# Nu6509_v3.net
KiCad netlist of a schematic drawn in EAGLE
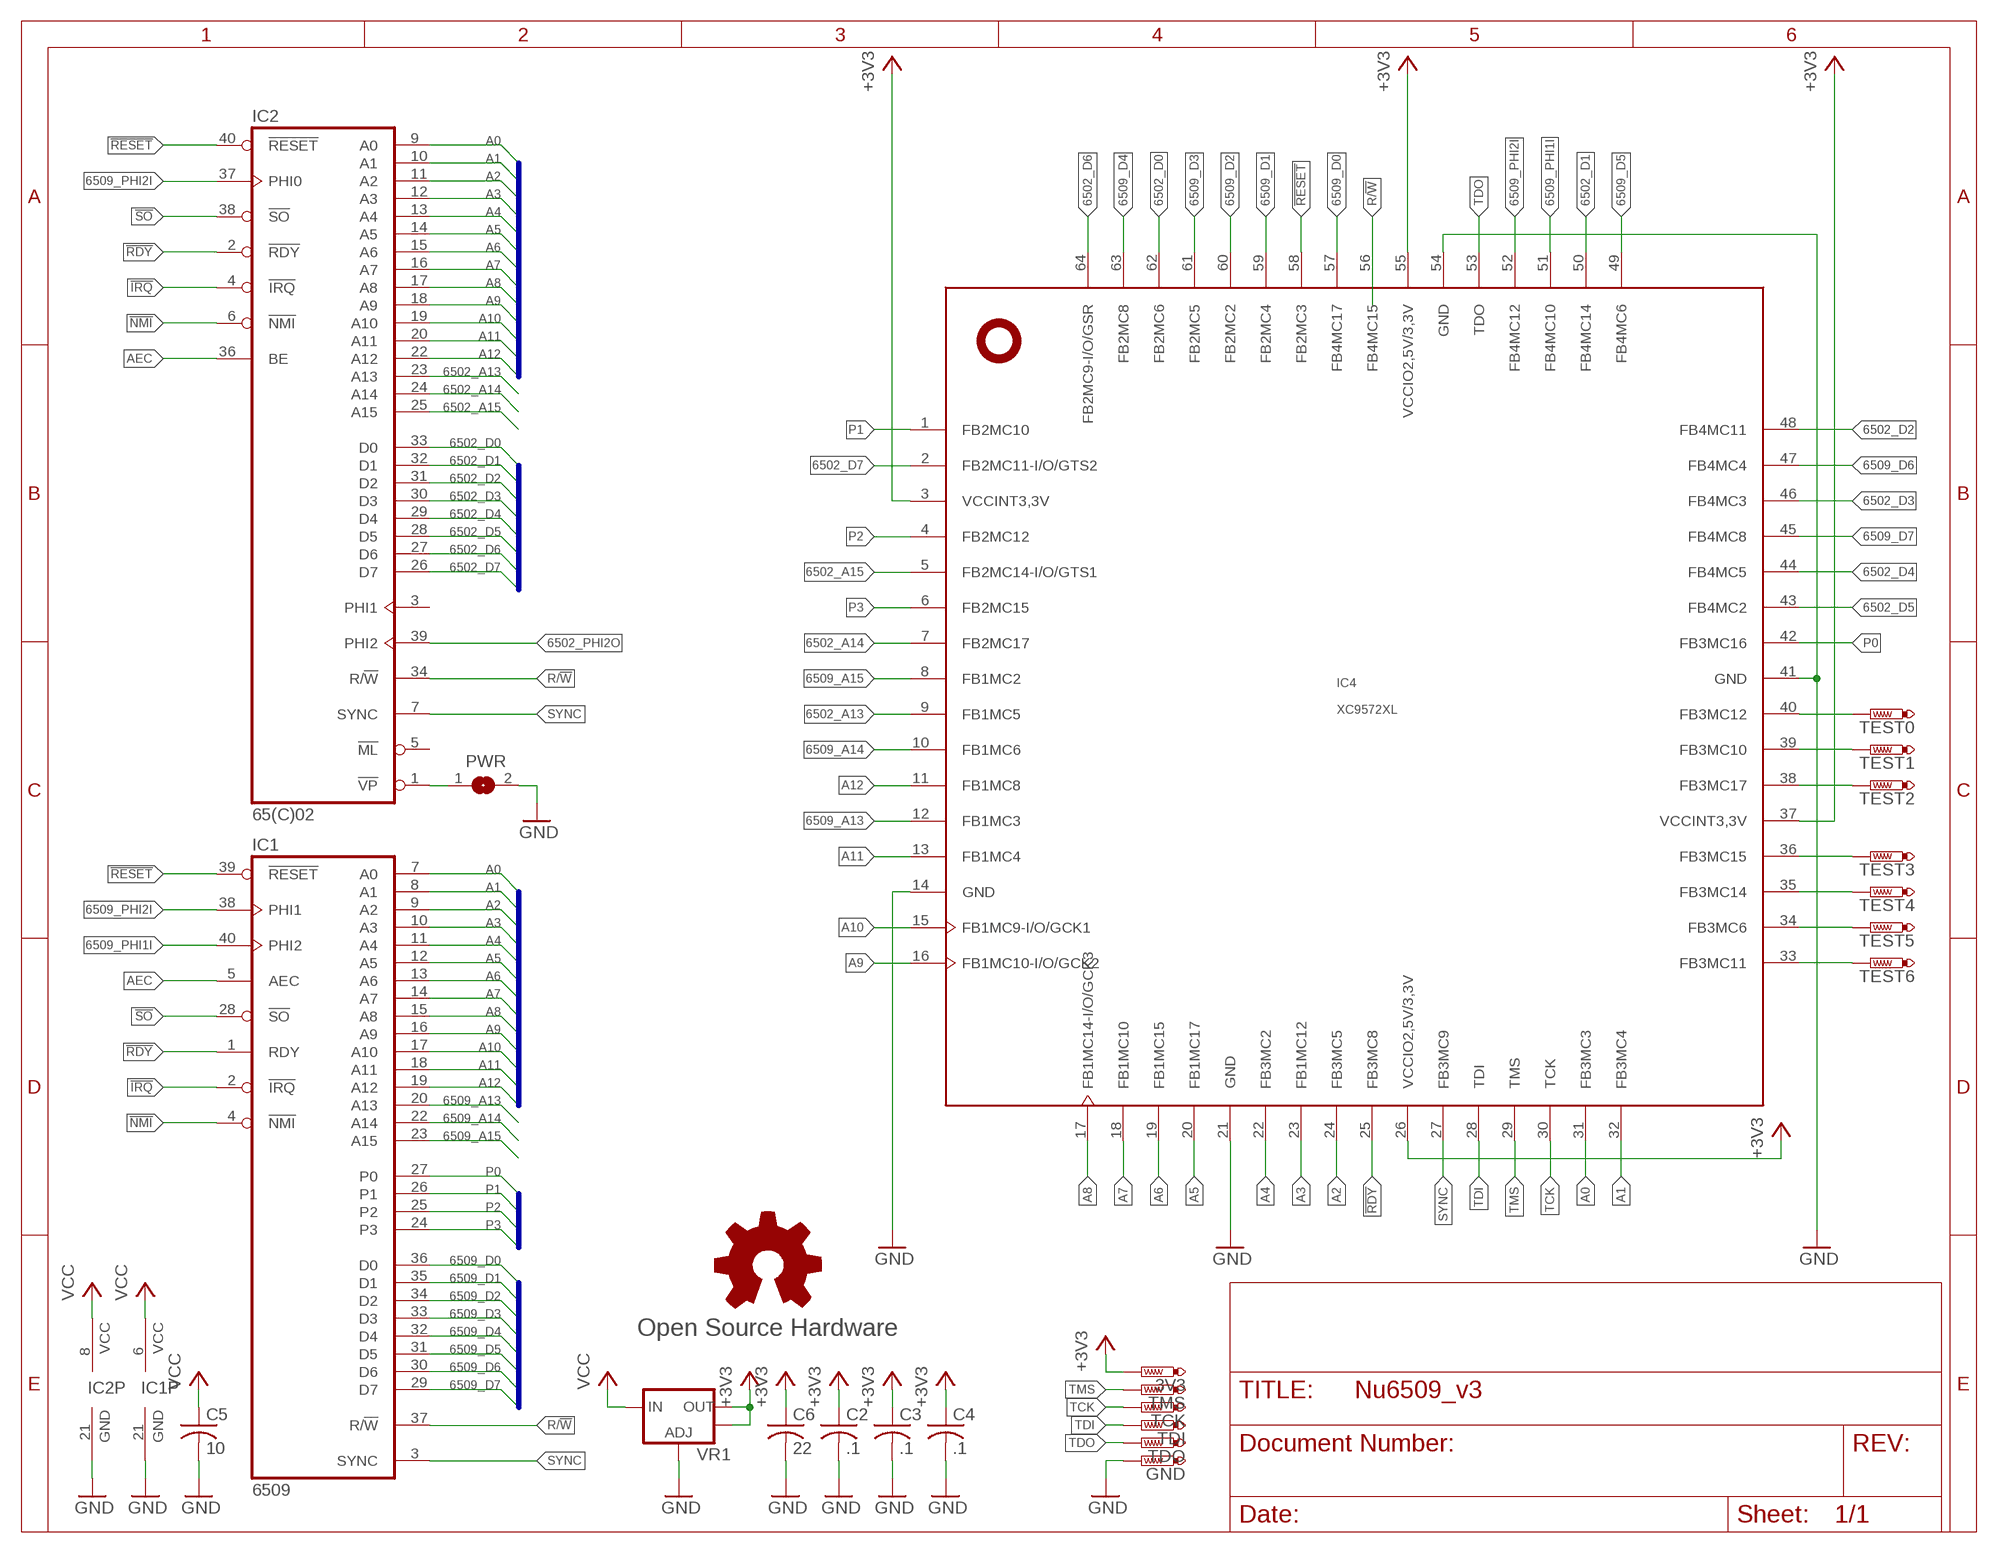
[diagram p0: schematic, sheet 1]

(export (version "E")
  (design (tool "Eeschema 10.0.6"))
  (components
    (comp (ref "3V3")
      (value "PTR1TP08R")
      (footprint "eagle-import:TP08R")
      (libsource (lib "eagle-import") (part "PTR1TP08R"))
    )
    (comp (ref "C2")
      (value ".1")
      (footprint "eagle-import:C0402")
      (libsource (lib "eagle-import") (part "C-USC0402"))
    )
    (comp (ref "C3")
      (value ".1")
      (footprint "eagle-import:C0402")
      (libsource (lib "eagle-import") (part "C-USC0402"))
    )
    (comp (ref "C4")
      (value ".1")
      (footprint "eagle-import:C0402")
      (libsource (lib "eagle-import") (part "C-USC0402"))
    )
    (comp (ref "C5")
      (value "10")
      (footprint "eagle-import:C0805")
      (libsource (lib "eagle-import") (part "C-USC0805"))
    )
    (comp (ref "C6")
      (value "22")
      (footprint "eagle-import:C0805")
      (libsource (lib "eagle-import") (part "C-USC0805"))
    )
    (comp (ref "GND")
      (value "PTR1TP08R")
      (footprint "eagle-import:TP08R")
      (libsource (lib "eagle-import") (part "PTR1TP08R"))
    )
    (comp (ref "GOLD_ORB_SM1")
      (value "Open Source Hardware")
      (footprint "eagle-import:OSHW_5MM")
      (libsource (lib "eagle-import") (part "OSHWLOGOLOGO5MM"))
    )
    (comp (ref "IC1")
      (value "6509")
      (footprint "eagle-import:DIL40-ROUNDPAD")
      (libsource (lib "eagle-import") (part "6509-RP"))
    )
    (comp (ref "IC2")
      (value "65(C)02")
      (footprint "eagle-import:DIL40-ROUNDPAD")
      (libsource (lib "eagle-import") (part "W65C02SP-R"))
    )
    (comp (ref "IC4")
      (value "XC9572XL")
      (footprint "eagle-import:VQFP64")
      (libsource (lib "eagle-import") (part "XC9572XLVQG64"))
    )
    (comp (ref "PWR") (value "SJ") (footprint "eagle-import:SJ") (libsource (lib "eagle-import") (part "SJ")))
    (comp (ref "TCK")
      (value "PTR1TP08R")
      (footprint "eagle-import:TP08R")
      (libsource (lib "eagle-import") (part "PTR1TP08R"))
    )
    (comp (ref "TDI")
      (value "PTR1TP08R")
      (footprint "eagle-import:TP08R")
      (libsource (lib "eagle-import") (part "PTR1TP08R"))
    )
    (comp (ref "TDO")
      (value "PTR1TP08R")
      (footprint "eagle-import:TP08R")
      (libsource (lib "eagle-import") (part "PTR1TP08R"))
    )
    (comp (ref "TEST0")
      (value "PTR1TP08R")
      (footprint "eagle-import:TP08R")
      (libsource (lib "eagle-import") (part "PTR1TP08R"))
    )
    (comp (ref "TEST1")
      (value "PTR1TP08R")
      (footprint "eagle-import:TP08R")
      (libsource (lib "eagle-import") (part "PTR1TP08R"))
    )
    (comp (ref "TEST2")
      (value "PTR1TP08R")
      (footprint "eagle-import:TP08R")
      (libsource (lib "eagle-import") (part "PTR1TP08R"))
    )
    (comp (ref "TEST3")
      (value "PTR1TP08R")
      (footprint "eagle-import:TP08R")
      (libsource (lib "eagle-import") (part "PTR1TP08R"))
    )
    (comp (ref "TEST4")
      (value "PTR1TP08R")
      (footprint "eagle-import:TP08R")
      (libsource (lib "eagle-import") (part "PTR1TP08R"))
    )
    (comp (ref "TEST5")
      (value "PTR1TP08R")
      (footprint "eagle-import:TP08R")
      (libsource (lib "eagle-import") (part "PTR1TP08R"))
    )
    (comp (ref "TEST6")
      (value "PTR1TP08R")
      (footprint "eagle-import:TP08R")
      (libsource (lib "eagle-import") (part "PTR1TP08R"))
    )
    (comp (ref "TMS")
      (value "PTR1TP08R")
      (footprint "eagle-import:TP08R")
      (libsource (lib "eagle-import") (part "PTR1TP08R"))
    )
    (comp (ref "VR1")
      (value "V_REG_LM1117SOT223")
      (footprint "eagle-import:SOT223")
      (libsource (lib "eagle-import") (part "V_REG_LM1117SOT223"))
    )
  )
  (nets
    (net (code "1") (name "+3V3") (class "Default")
      (node (ref "3V3") (pin "TP") (pinfunction "TP_TP") (pintype "input"))
      (node (ref "C2") (pin "1") (pinfunction "1_1") (pintype "passive"))
      (node (ref "C3") (pin "1") (pinfunction "1_1") (pintype "passive"))
      (node (ref "C4") (pin "1") (pinfunction "1_1") (pintype "passive"))
      (node (ref "C6") (pin "1") (pinfunction "1_1") (pintype "passive"))
      (node (ref "IC4") (pin "26") (pinfunction "VCCIO2,5V/3,3V_26") (pintype "power_in"))
      (node (ref "IC4") (pin "3") (pinfunction "VCCINT3,3V_3") (pintype "power_in"))
      (node (ref "IC4") (pin "37") (pinfunction "VCCINT3,3V_37") (pintype "power_in"))
      (node (ref "IC4") (pin "55") (pinfunction "VCCIO2,5V/3,3V_55") (pintype "power_in"))
      (node (ref "VR1") (pin "2") (pinfunction "OUT_2") (pintype "output"))
      (node (ref "VR1") (pin "4") (pinfunction "OUT_4") (pintype "output"))
    )
    (net (code "2") (name "/R{slash}~{W}") (class "Default")
      (node (ref "IC1") (pin "37") (pinfunction "R/~{W}_37") (pintype "output"))
      (node (ref "IC2") (pin "34") (pinfunction "R/~{W}_34") (pintype "output"))
      (node (ref "IC4") (pin "56") (pinfunction "FB4MC15_56") (pintype "bidirectional"))
    )
    (net (code "3") (name "/~{IRQ}") (class "Default")
      (node (ref "IC1") (pin "2") (pinfunction "~{IRQ}_2") (pintype "input"))
      (node (ref "IC2") (pin "4") (pinfunction "~{IRQ}_4") (pintype "input"))
    )
    (net (code "4") (name "/~{NMI}") (class "Default")
      (node (ref "IC1") (pin "4") (pinfunction "~{NMI}_4") (pintype "input"))
      (node (ref "IC2") (pin "6") (pinfunction "~{NMI}_6") (pintype "input"))
    )
    (net (code "5") (name "/~{RDY}") (class "Default")
      (node (ref "IC1") (pin "1") (pinfunction "RDY_1") (pintype "input"))
      (node (ref "IC2") (pin "2") (pinfunction "~{RDY}_2") (pintype "bidirectional"))
      (node (ref "IC4") (pin "25") (pinfunction "FB3MC8_25") (pintype "bidirectional"))
    )
    (net (code "6") (name "/~{RESET}") (class "Default")
      (node (ref "IC1") (pin "39") (pinfunction "~{RESET}_39") (pintype "input"))
      (node (ref "IC2") (pin "40") (pinfunction "~{RESET}_40") (pintype "input"))
      (node (ref "IC4") (pin "58") (pinfunction "FB2MC3_58") (pintype "bidirectional"))
    )
    (net (code "7") (name "/~{SO}") (class "Default")
      (node (ref "IC1") (pin "28") (pinfunction "~{SO}_28") (pintype "input"))
      (node (ref "IC2") (pin "38") (pinfunction "~{SO}_38") (pintype "input"))
    )
    (net (code "8") (name "6502_A13") (class "Default")
      (node (ref "IC2") (pin "23") (pinfunction "A13_23") (pintype "bidirectional"))
      (node (ref "IC4") (pin "9") (pinfunction "FB1MC5_9") (pintype "bidirectional"))
    )
    (net (code "9") (name "6502_A14") (class "Default")
      (node (ref "IC2") (pin "24") (pinfunction "A14_24") (pintype "bidirectional"))
      (node (ref "IC4") (pin "7") (pinfunction "FB2MC17_7") (pintype "bidirectional"))
    )
    (net (code "10") (name "6502_A15") (class "Default")
      (node (ref "IC2") (pin "25") (pinfunction "A15_25") (pintype "bidirectional"))
      (node (ref "IC4") (pin "5") (pinfunction "FB2MC14-I/O/GTS1_5") (pintype "bidirectional"))
    )
    (net (code "11") (name "6502_D0") (class "Default")
      (node (ref "IC2") (pin "33") (pinfunction "D0_33") (pintype "bidirectional"))
      (node (ref "IC4") (pin "62") (pinfunction "FB2MC6_62") (pintype "bidirectional"))
    )
    (net (code "12") (name "6502_D1") (class "Default")
      (node (ref "IC2") (pin "32") (pinfunction "D1_32") (pintype "bidirectional"))
      (node (ref "IC4") (pin "50") (pinfunction "FB4MC14_50") (pintype "bidirectional"))
    )
    (net (code "13") (name "6502_D2") (class "Default")
      (node (ref "IC2") (pin "31") (pinfunction "D2_31") (pintype "bidirectional"))
      (node (ref "IC4") (pin "48") (pinfunction "FB4MC11_48") (pintype "bidirectional"))
    )
    (net (code "14") (name "6502_D3") (class "Default")
      (node (ref "IC2") (pin "30") (pinfunction "D3_30") (pintype "bidirectional"))
      (node (ref "IC4") (pin "46") (pinfunction "FB4MC3_46") (pintype "bidirectional"))
    )
    (net (code "15") (name "6502_D4") (class "Default")
      (node (ref "IC2") (pin "29") (pinfunction "D4_29") (pintype "bidirectional"))
      (node (ref "IC4") (pin "44") (pinfunction "FB4MC5_44") (pintype "bidirectional"))
    )
    (net (code "16") (name "6502_D5") (class "Default")
      (node (ref "IC2") (pin "28") (pinfunction "D5_28") (pintype "bidirectional"))
      (node (ref "IC4") (pin "43") (pinfunction "FB4MC2_43") (pintype "bidirectional"))
    )
    (net (code "17") (name "6502_D6") (class "Default")
      (node (ref "IC2") (pin "27") (pinfunction "D6_27") (pintype "bidirectional"))
      (node (ref "IC4") (pin "64") (pinfunction "FB2MC9-I/O/GSR_64") (pintype "bidirectional"))
    )
    (net (code "18") (name "6502_D7") (class "Default")
      (node (ref "IC2") (pin "26") (pinfunction "D7_26") (pintype "bidirectional"))
      (node (ref "IC4") (pin "2") (pinfunction "FB2MC11-I/O/GTS2_2") (pintype "bidirectional"))
    )
    (net (code "19") (name "6502_PHI2O") (class "Default")
      (node (ref "IC2") (pin "39") (pinfunction "PHI2_39") (pintype "output"))
    )
    (net (code "20") (name "6509_A13") (class "Default")
      (node (ref "IC1") (pin "20") (pinfunction "A13_20") (pintype "output"))
      (node (ref "IC4") (pin "12") (pinfunction "FB1MC3_12") (pintype "bidirectional"))
    )
    (net (code "21") (name "6509_A14") (class "Default")
      (node (ref "IC1") (pin "22") (pinfunction "A14_22") (pintype "output"))
      (node (ref "IC4") (pin "10") (pinfunction "FB1MC6_10") (pintype "bidirectional"))
    )
    (net (code "22") (name "6509_A15") (class "Default")
      (node (ref "IC1") (pin "23") (pinfunction "A15_23") (pintype "output"))
      (node (ref "IC4") (pin "8") (pinfunction "FB1MC2_8") (pintype "bidirectional"))
    )
    (net (code "23") (name "6509_D0") (class "Default")
      (node (ref "IC1") (pin "36") (pinfunction "D0_36") (pintype "bidirectional"))
      (node (ref "IC4") (pin "57") (pinfunction "FB4MC17_57") (pintype "bidirectional"))
    )
    (net (code "24") (name "6509_D1") (class "Default")
      (node (ref "IC1") (pin "35") (pinfunction "D1_35") (pintype "bidirectional"))
      (node (ref "IC4") (pin "59") (pinfunction "FB2MC4_59") (pintype "bidirectional"))
    )
    (net (code "25") (name "6509_D2") (class "Default")
      (node (ref "IC1") (pin "34") (pinfunction "D2_34") (pintype "bidirectional"))
      (node (ref "IC4") (pin "60") (pinfunction "FB2MC2_60") (pintype "bidirectional"))
    )
    (net (code "26") (name "6509_D3") (class "Default")
      (node (ref "IC1") (pin "33") (pinfunction "D3_33") (pintype "bidirectional"))
      (node (ref "IC4") (pin "61") (pinfunction "FB2MC5_61") (pintype "bidirectional"))
    )
    (net (code "27") (name "6509_D4") (class "Default")
      (node (ref "IC1") (pin "32") (pinfunction "D4_32") (pintype "bidirectional"))
      (node (ref "IC4") (pin "63") (pinfunction "FB2MC8_63") (pintype "bidirectional"))
    )
    (net (code "28") (name "6509_D5") (class "Default")
      (node (ref "IC1") (pin "31") (pinfunction "D5_31") (pintype "bidirectional"))
      (node (ref "IC4") (pin "49") (pinfunction "FB4MC6_49") (pintype "bidirectional"))
    )
    (net (code "29") (name "6509_D6") (class "Default")
      (node (ref "IC1") (pin "30") (pinfunction "D6_30") (pintype "bidirectional"))
      (node (ref "IC4") (pin "47") (pinfunction "FB4MC4_47") (pintype "bidirectional"))
    )
    (net (code "30") (name "6509_D7") (class "Default")
      (node (ref "IC1") (pin "29") (pinfunction "D7_29") (pintype "bidirectional"))
      (node (ref "IC4") (pin "45") (pinfunction "FB4MC8_45") (pintype "bidirectional"))
    )
    (net (code "31") (name "6509_PHI1I") (class "Default")
      (node (ref "IC1") (pin "40") (pinfunction "PHI2_40") (pintype "input"))
      (node (ref "IC4") (pin "51") (pinfunction "FB4MC10_51") (pintype "bidirectional"))
    )
    (net (code "32") (name "6509_PHI2I") (class "Default")
      (node (ref "IC1") (pin "38") (pinfunction "PHI1_38") (pintype "input"))
      (node (ref "IC2") (pin "37") (pinfunction "PHI0_37") (pintype "input"))
      (node (ref "IC4") (pin "52") (pinfunction "FB4MC12_52") (pintype "bidirectional"))
    )
    (net (code "33") (name "A0") (class "Default")
      (node (ref "IC1") (pin "7") (pinfunction "A0_7") (pintype "output"))
      (node (ref "IC2") (pin "9") (pinfunction "A0_9") (pintype "bidirectional"))
      (node (ref "IC4") (pin "31") (pinfunction "FB3MC3_31") (pintype "bidirectional"))
    )
    (net (code "34") (name "A1") (class "Default")
      (node (ref "IC1") (pin "8") (pinfunction "A1_8") (pintype "output"))
      (node (ref "IC2") (pin "10") (pinfunction "A1_10") (pintype "bidirectional"))
      (node (ref "IC4") (pin "32") (pinfunction "FB3MC4_32") (pintype "bidirectional"))
    )
    (net (code "35") (name "A2") (class "Default")
      (node (ref "IC1") (pin "9") (pinfunction "A2_9") (pintype "output"))
      (node (ref "IC2") (pin "11") (pinfunction "A2_11") (pintype "bidirectional"))
      (node (ref "IC4") (pin "24") (pinfunction "FB3MC5_24") (pintype "bidirectional"))
    )
    (net (code "36") (name "A3") (class "Default")
      (node (ref "IC1") (pin "10") (pinfunction "A3_10") (pintype "output"))
      (node (ref "IC2") (pin "12") (pinfunction "A3_12") (pintype "bidirectional"))
      (node (ref "IC4") (pin "23") (pinfunction "FB1MC12_23") (pintype "bidirectional"))
    )
    (net (code "37") (name "A4") (class "Default")
      (node (ref "IC1") (pin "11") (pinfunction "A4_11") (pintype "output"))
      (node (ref "IC2") (pin "13") (pinfunction "A4_13") (pintype "bidirectional"))
      (node (ref "IC4") (pin "22") (pinfunction "FB3MC2_22") (pintype "bidirectional"))
    )
    (net (code "38") (name "A5") (class "Default")
      (node (ref "IC1") (pin "12") (pinfunction "A5_12") (pintype "output"))
      (node (ref "IC2") (pin "14") (pinfunction "A5_14") (pintype "bidirectional"))
      (node (ref "IC4") (pin "20") (pinfunction "FB1MC17_20") (pintype "bidirectional"))
    )
    (net (code "39") (name "A6") (class "Default")
      (node (ref "IC1") (pin "13") (pinfunction "A6_13") (pintype "output"))
      (node (ref "IC2") (pin "15") (pinfunction "A6_15") (pintype "bidirectional"))
      (node (ref "IC4") (pin "19") (pinfunction "FB1MC15_19") (pintype "bidirectional"))
    )
    (net (code "40") (name "A7") (class "Default")
      (node (ref "IC1") (pin "14") (pinfunction "A7_14") (pintype "output"))
      (node (ref "IC2") (pin "16") (pinfunction "A7_16") (pintype "bidirectional"))
      (node (ref "IC4") (pin "18") (pinfunction "FB1MC10_18") (pintype "bidirectional"))
    )
    (net (code "41") (name "A8") (class "Default")
      (node (ref "IC1") (pin "15") (pinfunction "A8_15") (pintype "output"))
      (node (ref "IC2") (pin "17") (pinfunction "A8_17") (pintype "bidirectional"))
      (node (ref "IC4") (pin "17") (pinfunction "FB1MC14-I/O/GCK3_17") (pintype "bidirectional"))
    )
    (net (code "42") (name "A9") (class "Default")
      (node (ref "IC1") (pin "16") (pinfunction "A9_16") (pintype "output"))
      (node (ref "IC2") (pin "18") (pinfunction "A9_18") (pintype "bidirectional"))
      (node (ref "IC4") (pin "16") (pinfunction "FB1MC10-I/O/GCK2_16") (pintype "bidirectional"))
    )
    (net (code "43") (name "A10") (class "Default")
      (node (ref "IC1") (pin "17") (pinfunction "A10_17") (pintype "output"))
      (node (ref "IC2") (pin "19") (pinfunction "A10_19") (pintype "bidirectional"))
      (node (ref "IC4") (pin "15") (pinfunction "FB1MC9-I/O/GCK1_15") (pintype "bidirectional"))
    )
    (net (code "44") (name "A11") (class "Default")
      (node (ref "IC1") (pin "18") (pinfunction "A11_18") (pintype "output"))
      (node (ref "IC2") (pin "20") (pinfunction "A11_20") (pintype "bidirectional"))
      (node (ref "IC4") (pin "13") (pinfunction "FB1MC4_13") (pintype "bidirectional"))
    )
    (net (code "45") (name "A12") (class "Default")
      (node (ref "IC1") (pin "19") (pinfunction "A12_19") (pintype "output"))
      (node (ref "IC2") (pin "22") (pinfunction "A12_22") (pintype "bidirectional"))
      (node (ref "IC4") (pin "11") (pinfunction "FB1MC8_11") (pintype "bidirectional"))
    )
    (net (code "46") (name "AEC") (class "Default")
      (node (ref "IC1") (pin "5") (pinfunction "AEC_5") (pintype "input"))
      (node (ref "IC2") (pin "36") (pinfunction "BE_36") (pintype "input"))
    )
    (net (code "47") (name "GND") (class "Default")
      (node (ref "C2") (pin "2") (pinfunction "2_2") (pintype "passive"))
      (node (ref "C3") (pin "2") (pinfunction "2_2") (pintype "passive"))
      (node (ref "C4") (pin "2") (pinfunction "2_2") (pintype "passive"))
      (node (ref "C5") (pin "2") (pinfunction "2_2") (pintype "passive"))
      (node (ref "C6") (pin "2") (pinfunction "2_2") (pintype "passive"))
      (node (ref "GND") (pin "TP") (pinfunction "TP_TP") (pintype "input"))
      (node (ref "IC1") (pin "21") (pinfunction "GND_21") (pintype "power_in"))
      (node (ref "IC2") (pin "21") (pinfunction "GND_21") (pintype "power_in"))
      (node (ref "IC4") (pin "14") (pinfunction "GND_14") (pintype "power_in"))
      (node (ref "IC4") (pin "21") (pinfunction "GND_21") (pintype "power_in"))
      (node (ref "IC4") (pin "41") (pinfunction "GND_41") (pintype "power_in"))
      (node (ref "IC4") (pin "54") (pinfunction "GND_54") (pintype "power_in"))
      (node (ref "PWR") (pin "2") (pinfunction "2_2") (pintype "passive"))
      (node (ref "VR1") (pin "1") (pinfunction "ADJ_1") (pintype "input"))
    )
    (net (code "48") (name "Net-(IC2A-~{VP})") (class "Default")
      (node (ref "IC2") (pin "1") (pinfunction "~{VP}_1") (pintype "output"))
      (node (ref "PWR") (pin "1") (pinfunction "1_1") (pintype "passive"))
    )
    (net (code "49") (name "Net-(IC4-FB3MC6)") (class "Default")
      (node (ref "IC4") (pin "34") (pinfunction "FB3MC6_34") (pintype "bidirectional"))
      (node (ref "TEST5") (pin "TP") (pinfunction "TP_TP") (pintype "input"))
    )
    (net (code "50") (name "Net-(IC4-FB3MC10)") (class "Default")
      (node (ref "IC4") (pin "39") (pinfunction "FB3MC10_39") (pintype "bidirectional"))
      (node (ref "TEST1") (pin "TP") (pinfunction "TP_TP") (pintype "input"))
    )
    (net (code "51") (name "Net-(IC4-FB3MC11)") (class "Default")
      (node (ref "IC4") (pin "33") (pinfunction "FB3MC11_33") (pintype "bidirectional"))
      (node (ref "TEST6") (pin "TP") (pinfunction "TP_TP") (pintype "input"))
    )
    (net (code "52") (name "Net-(IC4-FB3MC12)") (class "Default")
      (node (ref "IC4") (pin "40") (pinfunction "FB3MC12_40") (pintype "bidirectional"))
      (node (ref "TEST0") (pin "TP") (pinfunction "TP_TP") (pintype "input"))
    )
    (net (code "53") (name "Net-(IC4-FB3MC14)") (class "Default")
      (node (ref "IC4") (pin "35") (pinfunction "FB3MC14_35") (pintype "bidirectional"))
      (node (ref "TEST4") (pin "TP") (pinfunction "TP_TP") (pintype "input"))
    )
    (net (code "54") (name "Net-(IC4-FB3MC15)") (class "Default")
      (node (ref "IC4") (pin "36") (pinfunction "FB3MC15_36") (pintype "bidirectional"))
      (node (ref "TEST3") (pin "TP") (pinfunction "TP_TP") (pintype "input"))
    )
    (net (code "55") (name "Net-(IC4-FB3MC17)") (class "Default")
      (node (ref "IC4") (pin "38") (pinfunction "FB3MC17_38") (pintype "bidirectional"))
      (node (ref "TEST2") (pin "TP") (pinfunction "TP_TP") (pintype "input"))
    )
    (net (code "56") (name "P0") (class "Default")
      (node (ref "IC1") (pin "27") (pinfunction "P0_27") (pintype "output"))
      (node (ref "IC4") (pin "42") (pinfunction "FB3MC16_42") (pintype "bidirectional"))
    )
    (net (code "57") (name "P1") (class "Default")
      (node (ref "IC1") (pin "26") (pinfunction "P1_26") (pintype "output"))
      (node (ref "IC4") (pin "1") (pinfunction "FB2MC10_1") (pintype "bidirectional"))
    )
    (net (code "58") (name "P2") (class "Default")
      (node (ref "IC1") (pin "25") (pinfunction "P2_25") (pintype "output"))
      (node (ref "IC4") (pin "4") (pinfunction "FB2MC12_4") (pintype "bidirectional"))
    )
    (net (code "59") (name "P3") (class "Default")
      (node (ref "IC1") (pin "24") (pinfunction "P3_24") (pintype "output"))
      (node (ref "IC4") (pin "6") (pinfunction "FB2MC15_6") (pintype "bidirectional"))
    )
    (net (code "60") (name "SYNC") (class "Default")
      (node (ref "IC1") (pin "3") (pinfunction "SYNC_3") (pintype "output"))
      (node (ref "IC2") (pin "7") (pinfunction "SYNC_7") (pintype "output"))
      (node (ref "IC4") (pin "27") (pinfunction "FB3MC9_27") (pintype "bidirectional"))
    )
    (net (code "61") (name "TCK") (class "Default")
      (node (ref "IC4") (pin "30") (pinfunction "TCK_30") (pintype "bidirectional"))
      (node (ref "TCK") (pin "TP") (pinfunction "TP_TP") (pintype "input"))
    )
    (net (code "62") (name "TDI") (class "Default")
      (node (ref "IC4") (pin "28") (pinfunction "TDI_28") (pintype "bidirectional"))
      (node (ref "TDI") (pin "TP") (pinfunction "TP_TP") (pintype "input"))
    )
    (net (code "63") (name "TDO") (class "Default")
      (node (ref "IC4") (pin "53") (pinfunction "TDO_53") (pintype "bidirectional"))
      (node (ref "TDO") (pin "TP") (pinfunction "TP_TP") (pintype "input"))
    )
    (net (code "64") (name "TMS") (class "Default")
      (node (ref "IC4") (pin "29") (pinfunction "TMS_29") (pintype "bidirectional"))
      (node (ref "TMS") (pin "TP") (pinfunction "TP_TP") (pintype "input"))
    )
    (net (code "65") (name "VCC") (class "Default")
      (node (ref "C5") (pin "1") (pinfunction "1_1") (pintype "passive"))
      (node (ref "IC1") (pin "6") (pinfunction "VCC_6") (pintype "power_in"))
      (node (ref "IC2") (pin "8") (pinfunction "VCC_8") (pintype "power_in"))
      (node (ref "VR1") (pin "3") (pinfunction "IN_3") (pintype "input"))
    )
    (net (code "66") (name "unconnected-(IC2A-PHI1-Pad3)") (class "Default")
      (node (ref "IC2") (pin "3") (pinfunction "PHI1_3") (pintype "output"))
    )
    (net (code "67") (name "unconnected-(IC2A-~{ML}-Pad5)") (class "Default")
      (node (ref "IC2") (pin "5") (pinfunction "~{ML}_5") (pintype "output"))
    )
  )
)
